# Microcontroller.net
KiCad netlist of a schematic drawn in Altium Designer
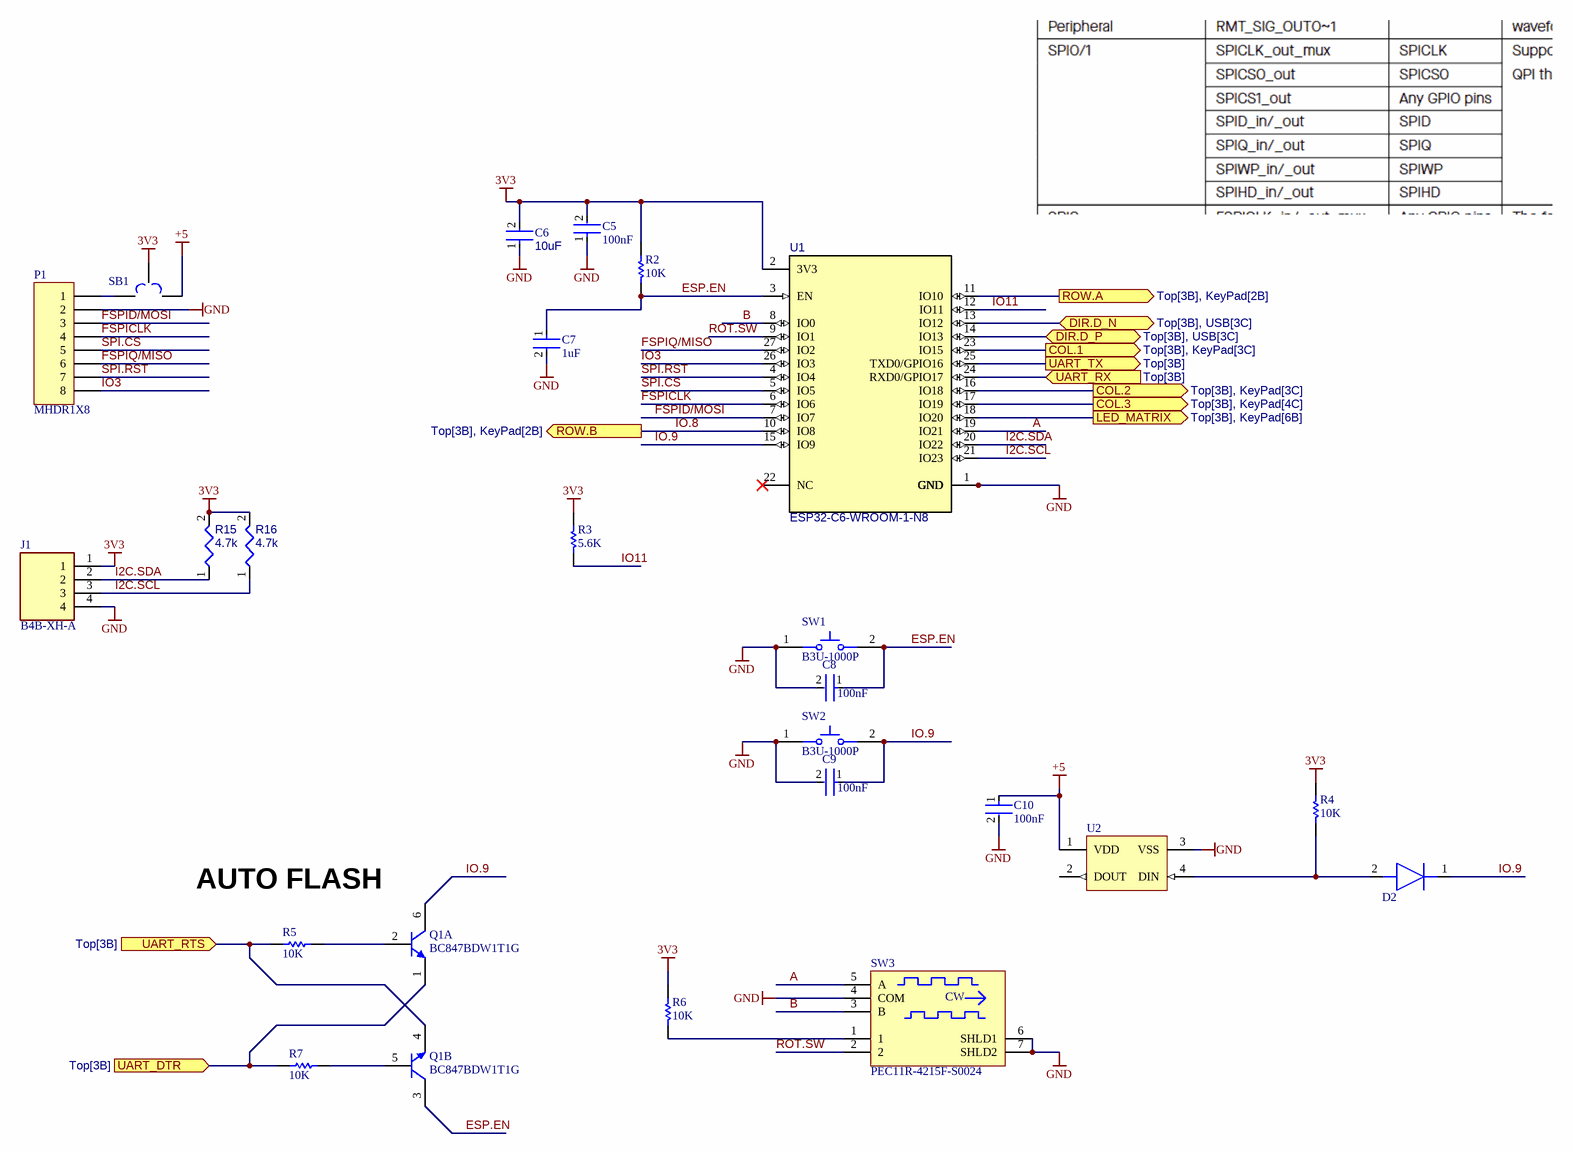
[diagram p0: Microcontroller.SchDoc]

(export (version "E")
  (design (tool "Eeschema 10.0.6"))
  (components
    (comp (ref "C5")
      (value "100nF")
      (footprint "FP-GRM188-0_1-e0_2_0_55-IPC_A")
      (description "Chip Multilayer Ceramic Capacitors for General Purpose, 0603, 10uF, X5R, 15%, 20%, 6.3V")
      (fields (field (name "VOLTAGE") "6.3V") (field (name "TOLERANCE") "20%"))
      (libsource (lib "Altium Content Vault") (part "02cd4be3c70576c341d710602a673aa"))
    )
    (comp (ref "C6")
      (value "C1608X5R1E106M080AC")
      (footprint "FP-C1608-080-IPC_A")
      (description "CAP CER 10UF 25V X5R 0603")
      (fields (field (name "TOLERANCE") "20%") (field (name "CAPACITANCE") "10uF"))
      (libsource (lib "Altium Content Vault") (part "11868f565c42a9108669ba33697ecf6"))
    )
    (comp (ref "C7")
      (value "1uF")
      (footprint "FP-CC0603-DA-MFG")
      (description "CAP CER 1UF 16V X7R 0603")
      (fields (field (name "TOLERANCE") "0.1") (field (name "MANUFACTURER") "YAGEO"))
      (libsource (lib "Altium Content Vault") (part "11868f565c42a9108669ba33697ecf6"))
    )
    (comp (ref "C8")
      (value "100nF")
      (footprint "FP-GRM188-0_1-e0_2_0_55-IPC_A")
      (description "Chip Multilayer Ceramic Capacitors for General Purpose, 0603, 10uF, X5R, 15%, 20%, 6.3V")
      (fields (field (name "VOLTAGE") "6.3V") (field (name "TOLERANCE") "20%"))
      (libsource (lib "Altium Content Vault") (part "02cd4be3c70576c341d710602a673aa"))
    )
    (comp (ref "C9")
      (value "100nF")
      (footprint "FP-GRM188-0_1-e0_2_0_55-IPC_A")
      (description "Chip Multilayer Ceramic Capacitors for General Purpose, 0603, 10uF, X5R, 15%, 20%, 6.3V")
      (fields (field (name "VOLTAGE") "6.3V") (field (name "TOLERANCE") "20%"))
      (libsource (lib "Altium Content Vault") (part "02cd4be3c70576c341d710602a673aa"))
    )
    (comp (ref "C10")
      (value "100nF")
      (footprint "FP-GRM188-0_1-e0_2_0_55-IPC_A")
      (description "Chip Multilayer Ceramic Capacitors for General Purpose, 0603, 10uF, X5R, 15%, 20%, 6.3V")
      (fields (field (name "VOLTAGE") "6.3V") (field (name "TOLERANCE") "20%"))
      (libsource (lib "Altium Content Vault") (part "02cd4be3c70576c341d710602a673aa"))
    )
    (comp (ref "D2")
      (value "NSVR1020MW2T1G")
      (footprint "SOD2512X110N")
      (description "Diode")
      (fields (field (name "MOUSER PART NUMBER") "863-NSVR1020MW2T1G"))
      (libsource (lib "Curtin Motorsport Team") (part "NSVR1020MW2T1G"))
    )
    (comp (ref "J1")
      (value "B4B-XH-A")
      (footprint "B4BXHA")
      (description "Connector")
      (libsource (lib "Curtin Motorsport Team") (part "B4B-XH-A"))
    )
    (comp (ref "P1")
      (value "MHDR1X8")
      (footprint "MHDR1X8")
      (description "Header, 8-Pin")
      (fields (field (name "PUBLISHER") "Altium Limited"))
      (libsource (lib "Curtin Motorsport Team") (part "Header 8H"))
    )
    (comp (ref "Q1")
      (value "BC847BDW1T1G")
      (footprint "ONSC-SOT-363-6-419B-02_W_V")
      (description "Dual General Purpose Transistors, NPN, 6-Pin SOT-363, Pb-Free, Tape and Reel")
      (fields (field (name "MANUFACTURER") "On Semiconductor"))
      (libsource (lib "Altium Content Vault") (part "ONSC-NPN_NPN-6_F"))
    )
    (comp (ref "R2")
      (value "10K")
      (footprint "RESC1609X50X30NL10T20")
      (fields (field (name "PART NUMBER") "CRCW060356K0FKEA") (field (name "MANUFACTURER") "Vishay Dale"))
      (libsource (lib "Altium Content Vault") (part "RES"))
    )
    (comp (ref "R3")
      (value "5.6K")
      (footprint "RESC1609X50X30NL10T20")
      (fields (field (name "PART NUMBER") "CRCW060356K0FKEA") (field (name "MANUFACTURER") "Vishay Dale"))
      (libsource (lib "Altium Content Vault") (part "RES"))
    )
    (comp (ref "R4")
      (value "10K")
      (footprint "RESC1609X50X30NL10T20")
      (fields (field (name "PART NUMBER") "CRCW060356K0FKEA") (field (name "MANUFACTURER") "Vishay Dale"))
      (libsource (lib "Altium Content Vault") (part "RES"))
    )
    (comp (ref "R5")
      (value "10K")
      (footprint "RESC1609X50X30NL10T20")
      (fields (field (name "PART NUMBER") "CRCW060356K0FKEA") (field (name "MANUFACTURER") "Vishay Dale"))
      (libsource (lib "Altium Content Vault") (part "RES"))
    )
    (comp (ref "R6")
      (value "10K")
      (footprint "RESC1609X50X30NL10T20")
      (fields (field (name "PART NUMBER") "CRCW060356K0FKEA") (field (name "MANUFACTURER") "Vishay Dale"))
      (libsource (lib "Altium Content Vault") (part "RES"))
    )
    (comp (ref "R7")
      (value "10K")
      (footprint "RESC1609X50X30NL10T20")
      (fields (field (name "PART NUMBER") "CRCW060356K0FKEA") (field (name "MANUFACTURER") "Vishay Dale"))
      (libsource (lib "Altium Content Vault") (part "RES"))
    )
    (comp (ref "R15")
      (value "4.7k")
      (footprint "RESC1608X55X25ML10T15")
      (description "Chip Resistor, 4.7 KOhm, +/- 1%, 0.1 W, -55 to 155 degC, 0603 (1608 Metric)")
      (fields (field (name "POWER") "100mW") (field (name "TOLERANCE") "1%"))
      (libsource (lib "Curtin Motorsport Team") (part "RES"))
    )
    (comp (ref "R16")
      (value "4.7k")
      (footprint "RESC1608X55X25ML10T15")
      (description "Chip Resistor, 4.7 KOhm, +/- 1%, 0.1 W, -55 to 155 degC, 0603 (1608 Metric)")
      (fields (field (name "POWER") "100mW") (field (name "TOLERANCE") "1%"))
      (libsource (lib "Curtin Motorsport Team") (part "RES"))
    )
    (comp (ref "SB1")
      (value "3 POS Solder Bridge")
      (footprint "3 POS Solder Bridge-Footprint-1")
      (description "3 position solder bridge")
      (fields (field (name "SOURCE") "StrainComponents.SchLib"))
      (libsource (lib "Curtin Motorsport Team") (part "3 POS SB"))
    )
    (comp (ref "SW1")
      (value "B3U-1000P")
      (footprint "OMRON-B3U-1000_V")
      (description "Tactile Switch, SPST-NO, 0.05 A, 12 V, -25 to 70 degC, 2-Pin SMD, RoHS, Tape and Reel")
      (fields (field (name "MANUFACTURER") "Omron Electronic Components"))
      (libsource (lib "Curtin Motorsport Team") (part "SW-SPST-NO-2"))
    )
    (comp (ref "SW2")
      (value "B3U-1000P")
      (footprint "OMRON-B3U-1000_V")
      (description "Tactile Switch, SPST-NO, 0.05 A, 12 V, -25 to 70 degC, 2-Pin SMD, RoHS, Tape and Reel")
      (fields (field (name "MANUFACTURER") "Omron Electronic Components"))
      (libsource (lib "Curtin Motorsport Team") (part "SW-SPST-NO-2"))
    )
    (comp (ref "SW3")
      (value "PEC11R-4215F-S0024")
      (footprint "BOUR-PEC11R-4XXXF-SXXXX_V")
      (description "12 mm Incremental Encoder, 24 Detent, -30 to 70 degC, 5-Pin THD, RoHS, Bulk")
      (fields (field (name "MANUFACTURER") "Bourns"))
      (libsource (lib "Curtin Motorsport Team") (part "SW-ENCODER-5"))
    )
    (comp (ref "U1")
      (value "ESP32-C6-WROOM-1-N8")
      (footprint "ESP32-C6-WROOM-1-N8-Footprint-1")
      (description "ESP32-C6-WROOM-1-N8 Engineering Module - 8 MB Quad SPI Flash")
      (libsource (lib "Curtin Motorsport Team") (part "ESP32-C6-WROOM-1-N8-Symbol-1"))
    )
    (comp (ref "U2")
      (value "WS2812B")
      (footprint "ADAI-WS2812B_V")
      (fields (field (name "MANUFACTURER") "Adafruit Industries"))
      (libsource (lib "Curtin Motorsport Team") (part "ADAI-WS2812B-4"))
    )
  )
  (nets
    (net (code "1") (name "+5") (class "Default")
      (node (ref "C10") (pin "1") (pinfunction "1_1") (pintype "passive"))
      (node (ref "SB1") (pin "3") (pinfunction "3_3") (pintype "passive"))
      (node (ref "U2") (pin "1") (pinfunction "VDD_1") (pintype "power_in"))
    )
    (net (code "2") (name "/A") (class "Default")
      (node (ref "SW3") (pin "5") (pinfunction "A_5") (pintype "passive"))
      (node (ref "U1") (pin "19") (pinfunction "IO21_19") (pintype "bidirectional"))
    )
    (net (code "3") (name "/B") (class "Default")
      (node (ref "SW3") (pin "3") (pinfunction "B_3") (pintype "passive"))
      (node (ref "U1") (pin "8") (pinfunction "IO0_8") (pintype "bidirectional"))
    )
    (net (code "4") (name "/COL.1") (class "Default")
      (node (ref "U1") (pin "23") (pinfunction "IO15_23") (pintype "bidirectional"))
    )
    (net (code "5") (name "/COL.2") (class "Default")
      (node (ref "U1") (pin "16") (pinfunction "IO18_16") (pintype "bidirectional"))
    )
    (net (code "6") (name "/COL.3") (class "Default")
      (node (ref "U1") (pin "17") (pinfunction "IO19_17") (pintype "bidirectional"))
    )
    (net (code "7") (name "/DIR.D_N") (class "Default")
      (node (ref "U1") (pin "13") (pinfunction "IO12_13") (pintype "bidirectional"))
    )
    (net (code "8") (name "/DIR.D_P") (class "Default")
      (node (ref "U1") (pin "14") (pinfunction "IO13_14") (pintype "bidirectional"))
    )
    (net (code "9") (name "/ESP.EN") (class "Default")
      (node (ref "C7") (pin "1") (pinfunction "1_1") (pintype "passive"))
      (node (ref "C8") (pin "1") (pinfunction "1_1") (pintype "passive"))
      (node (ref "Q1") (pin "3") (pinfunction "C_3") (pintype "passive"))
      (node (ref "R2") (pin "2") (pinfunction "2_2") (pintype "passive"))
      (node (ref "SW1") (pin "2") (pinfunction "2_2") (pintype "passive"))
      (node (ref "U1") (pin "3") (pinfunction "EN_3") (pintype "input"))
    )
    (net (code "10") (name "/FSPICLK") (class "Default")
      (node (ref "P1") (pin "4") (pinfunction "4_4") (pintype "passive"))
      (node (ref "U1") (pin "6") (pinfunction "IO6_6") (pintype "bidirectional"))
    )
    (net (code "11") (name "/FSPID{slash}MOSI") (class "Default")
      (node (ref "P1") (pin "3") (pinfunction "3_3") (pintype "passive"))
      (node (ref "U1") (pin "7") (pinfunction "IO7_7") (pintype "bidirectional"))
    )
    (net (code "12") (name "/FSPIQ{slash}MISO") (class "Default")
      (node (ref "P1") (pin "6") (pinfunction "6_6") (pintype "passive"))
      (node (ref "U1") (pin "27") (pinfunction "IO2_27") (pintype "bidirectional"))
    )
    (net (code "13") (name "/I2C.SCL") (class "Default")
      (node (ref "J1") (pin "3") (pinfunction "3_3") (pintype "passive"))
      (node (ref "R16") (pin "1") (pinfunction "1_1") (pintype "passive"))
      (node (ref "U1") (pin "21") (pinfunction "IO23_21") (pintype "bidirectional"))
    )
    (net (code "14") (name "/I2C.SDA") (class "Default")
      (node (ref "J1") (pin "2") (pinfunction "2_2") (pintype "passive"))
      (node (ref "R15") (pin "1") (pinfunction "1_1") (pintype "passive"))
      (node (ref "U1") (pin "20") (pinfunction "IO22_20") (pintype "bidirectional"))
    )
    (net (code "15") (name "/IO.8") (class "Default")
      (node (ref "U1") (pin "10") (pinfunction "IO8_10") (pintype "bidirectional"))
    )
    (net (code "16") (name "/IO.9") (class "Default")
      (node (ref "C9") (pin "1") (pinfunction "1_1") (pintype "passive"))
      (node (ref "D2") (pin "1") (pinfunction "K_1") (pintype "passive"))
      (node (ref "Q1") (pin "6") (pinfunction "C_6") (pintype "passive"))
      (node (ref "SW2") (pin "2") (pinfunction "2_2") (pintype "passive"))
      (node (ref "U1") (pin "15") (pinfunction "IO9_15") (pintype "bidirectional"))
    )
    (net (code "17") (name "/IO3") (class "Default")
      (node (ref "P1") (pin "8") (pinfunction "8_8") (pintype "passive"))
      (node (ref "U1") (pin "26") (pinfunction "IO3_26") (pintype "bidirectional"))
    )
    (net (code "18") (name "/IO11") (class "Default")
      (node (ref "R3") (pin "2") (pinfunction "2_2") (pintype "passive"))
      (node (ref "U1") (pin "12") (pinfunction "IO11_12") (pintype "bidirectional"))
    )
    (net (code "19") (name "/LED_MATRIX") (class "Default")
      (node (ref "U1") (pin "18") (pinfunction "IO20_18") (pintype "bidirectional"))
    )
    (net (code "20") (name "/ROT.SW") (class "Default")
      (node (ref "SW3") (pin "2") (pinfunction "2_2") (pintype "passive"))
      (node (ref "U1") (pin "9") (pinfunction "IO1_9") (pintype "bidirectional"))
    )
    (net (code "21") (name "/ROW.A") (class "Default")
      (node (ref "U1") (pin "11") (pinfunction "IO10_11") (pintype "bidirectional"))
    )
    (net (code "22") (name "/SPI.CS") (class "Default")
      (node (ref "P1") (pin "5") (pinfunction "5_5") (pintype "passive"))
      (node (ref "U1") (pin "5") (pinfunction "IO5_5") (pintype "bidirectional"))
    )
    (net (code "23") (name "/SPI.RST") (class "Default")
      (node (ref "P1") (pin "7") (pinfunction "7_7") (pintype "passive"))
      (node (ref "U1") (pin "4") (pinfunction "IO4_4") (pintype "bidirectional"))
    )
    (net (code "24") (name "/UART_DTR") (class "Default")
      (node (ref "Q1") (pin "1") (pinfunction "E_1") (pintype "passive"))
      (node (ref "R7") (pin "1") (pinfunction "1_1") (pintype "passive"))
    )
    (net (code "25") (name "/UART_RTS") (class "Default")
      (node (ref "Q1") (pin "4") (pinfunction "E_4") (pintype "passive"))
      (node (ref "R5") (pin "1") (pinfunction "1_1") (pintype "passive"))
    )
    (net (code "26") (name "/UART_RX") (class "Default")
      (node (ref "U1") (pin "24") (pinfunction "RXD0/GPIO17_24") (pintype "bidirectional"))
    )
    (net (code "27") (name "/UART_TX") (class "Default")
      (node (ref "U1") (pin "25") (pinfunction "TXD0/GPIO16_25") (pintype "bidirectional"))
    )
    (net (code "28") (name "3V3") (class "Default")
      (node (ref "C5") (pin "2") (pinfunction "2_2") (pintype "passive"))
      (node (ref "C6") (pin "2") (pinfunction "2_2") (pintype "passive"))
      (node (ref "J1") (pin "1") (pinfunction "1_1") (pintype "passive"))
      (node (ref "R15") (pin "2") (pinfunction "2_2") (pintype "passive"))
      (node (ref "R16") (pin "2") (pinfunction "2_2") (pintype "passive"))
      (node (ref "R2") (pin "1") (pinfunction "1_1") (pintype "passive"))
      (node (ref "R3") (pin "1") (pinfunction "1_1") (pintype "passive"))
      (node (ref "R4") (pin "1") (pinfunction "1_1") (pintype "passive"))
      (node (ref "R6") (pin "1") (pinfunction "1_1") (pintype "passive"))
      (node (ref "SB1") (pin "2") (pinfunction "2_2") (pintype "passive"))
      (node (ref "U1") (pin "2") (pinfunction "3V3_2") (pintype "power_in"))
    )
    (net (code "29") (name "GND") (class "Default")
      (node (ref "C10") (pin "2") (pinfunction "2_2") (pintype "passive"))
      (node (ref "C5") (pin "1") (pinfunction "1_1") (pintype "passive"))
      (node (ref "C6") (pin "1") (pinfunction "1_1") (pintype "passive"))
      (node (ref "C7") (pin "2") (pinfunction "2_2") (pintype "passive"))
      (node (ref "C8") (pin "2") (pinfunction "2_2") (pintype "passive"))
      (node (ref "C9") (pin "2") (pinfunction "2_2") (pintype "passive"))
      (node (ref "J1") (pin "4") (pinfunction "4_4") (pintype "passive"))
      (node (ref "P1") (pin "2") (pinfunction "2_2") (pintype "passive"))
      (node (ref "SW1") (pin "1") (pinfunction "1_1") (pintype "passive"))
      (node (ref "SW2") (pin "1") (pinfunction "1_1") (pintype "passive"))
      (node (ref "SW3") (pin "4") (pinfunction "COM_4") (pintype "passive"))
      (node (ref "SW3") (pin "6") (pinfunction "SHLD1_6") (pintype "passive"))
      (node (ref "SW3") (pin "7") (pinfunction "SHLD2_7") (pintype "passive"))
      (node (ref "U1") (pin "1") (pinfunction "GND_1") (pintype "power_in"))
      (node (ref "U1") (pin "28") (pinfunction "GND_28") (pintype "power_in"))
      (node (ref "U1") (pin "29_1") (pinfunction "GND_29_1") (pintype "power_in"))
      (node (ref "U1") (pin "29_2") (pinfunction "GND_29_2") (pintype "power_in"))
      (node (ref "U1") (pin "29_3") (pinfunction "GND_29_3") (pintype "power_in"))
      (node (ref "U1") (pin "29_4") (pinfunction "GND_29_4") (pintype "power_in"))
      (node (ref "U1") (pin "29_5") (pinfunction "GND_29_5") (pintype "power_in"))
      (node (ref "U1") (pin "29_6") (pinfunction "GND_29_6") (pintype "power_in"))
      (node (ref "U1") (pin "29_7") (pinfunction "GND_29_7") (pintype "power_in"))
      (node (ref "U1") (pin "29_8") (pinfunction "GND_29_8") (pintype "power_in"))
      (node (ref "U1") (pin "29_9") (pinfunction "GND_29_9") (pintype "power_in"))
      (node (ref "U2") (pin "3") (pinfunction "VSS_3") (pintype "power_in"))
    )
    (net (code "30") (name "Net-(D2-A)") (class "Default")
      (node (ref "D2") (pin "2") (pinfunction "A_2") (pintype "passive"))
      (node (ref "R4") (pin "2") (pinfunction "2_2") (pintype "passive"))
      (node (ref "U2") (pin "4") (pinfunction "DIN_4") (pintype "input"))
    )
    (net (code "31") (name "Net-(P1-Pad1)") (class "Default")
      (node (ref "P1") (pin "1") (pinfunction "1_1") (pintype "passive"))
      (node (ref "SB1") (pin "1") (pinfunction "1_1") (pintype "passive"))
    )
    (net (code "32") (name "Net-(Q1A-B)") (class "Default")
      (node (ref "Q1") (pin "2") (pinfunction "B_2") (pintype "passive"))
      (node (ref "R5") (pin "2") (pinfunction "2_2") (pintype "passive"))
    )
    (net (code "33") (name "Net-(Q1B-B)") (class "Default")
      (node (ref "Q1") (pin "5") (pinfunction "B_5") (pintype "passive"))
      (node (ref "R7") (pin "2") (pinfunction "2_2") (pintype "passive"))
    )
    (net (code "34") (name "Net-(R6-Pad2)") (class "Default")
      (node (ref "R6") (pin "2") (pinfunction "2_2") (pintype "passive"))
      (node (ref "SW3") (pin "1") (pinfunction "1_1") (pintype "passive"))
    )
    (net (code "35") (name "unconnected-(U1-NC-Pad22)") (class "Default")
      (node (ref "U1") (pin "22") (pinfunction "NC_22") (pintype "passive+no_connect"))
    )
    (net (code "36") (name "unconnected-(U2-DOUT-Pad2)") (class "Default")
      (node (ref "U2") (pin "2") (pinfunction "DOUT_2") (pintype "output"))
    )
  )
)
